# 10-Power.net
KiCad netlist of a schematic drawn in Altium Designer
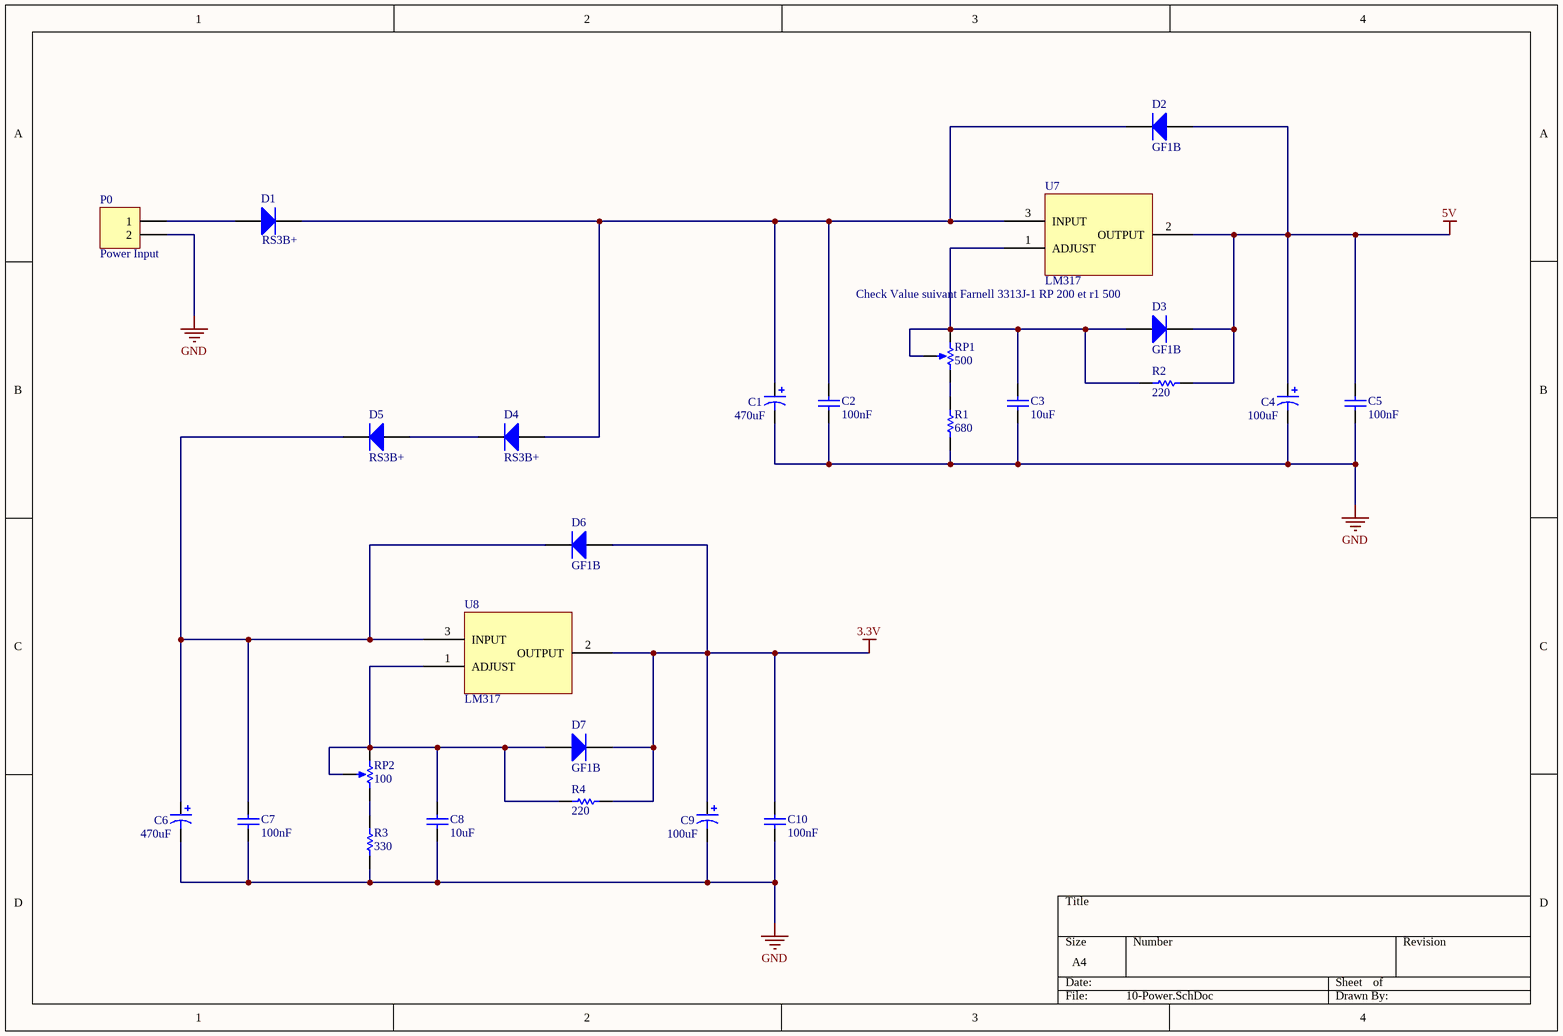
[diagram p0: 10-Power.SchDoc]

(export (version "E")
  (design (tool "Eeschema 10.0.6"))
  (components
    (comp (ref "C1")
      (value "470uF")
      (footprint "CAPA PANA SIZE D*")
      (description "Polarized Capacitor (Radial)")
      (libsource (lib "Miscellaneous Devices") (part "Cap Pol1"))
    )
    (comp (ref "C2")
      (value "100nF")
      (footprint "capa 1206")
      (description "Capacitor")
      (libsource (lib "Miscellaneous Devices") (part "Cap"))
    )
    (comp (ref "C3")
      (value "10uF")
      (footprint "capa 1206")
      (description "Capacitor")
      (libsource (lib "Miscellaneous Devices") (part "Cap"))
    )
    (comp (ref "C4")
      (value "100uF")
      (footprint "CAPA PANA SIZE D*")
      (description "Polarized Capacitor (Radial)")
      (libsource (lib "Miscellaneous Devices") (part "Cap Pol1"))
    )
    (comp (ref "C5")
      (value "100nF")
      (footprint "capa 1206")
      (description "Capacitor")
      (libsource (lib "Miscellaneous Devices") (part "Cap"))
    )
    (comp (ref "C6")
      (value "470uF")
      (footprint "CAPA PANA SIZE D*")
      (description "Polarized Capacitor (Radial)")
      (libsource (lib "Miscellaneous Devices") (part "Cap Pol1"))
    )
    (comp (ref "C7")
      (value "100nF")
      (footprint "capa 1206")
      (description "Capacitor")
      (libsource (lib "Miscellaneous Devices") (part "Cap"))
    )
    (comp (ref "C8")
      (value "10uF")
      (footprint "capa 1206")
      (description "Capacitor")
      (libsource (lib "Miscellaneous Devices") (part "Cap"))
    )
    (comp (ref "C9")
      (value "100uF")
      (footprint "CAPA PANA SIZE D*")
      (description "Polarized Capacitor (Radial)")
      (libsource (lib "Miscellaneous Devices") (part "Cap Pol1"))
    )
    (comp (ref "C10")
      (value "100nF")
      (footprint "capa 1206")
      (description "Capacitor")
      (libsource (lib "Miscellaneous Devices") (part "Cap"))
    )
    (comp (ref "D1")
      (value "RS3B+")
      (footprint "SMC Vishay")
      (description "Default Diode")
      (libsource (lib "Miscellaneous Devices") (part "Diode"))
    )
    (comp (ref "D2")
      (value "GF1B")
      (footprint "DO-214AC(SMA)")
      (description "Default Diode")
      (libsource (lib "Miscellaneous Devices") (part "Diode"))
    )
    (comp (ref "D3")
      (value "GF1B")
      (footprint "DO-214AC(SMA)")
      (description "Default Diode")
      (libsource (lib "Miscellaneous Devices") (part "Diode"))
    )
    (comp (ref "D4")
      (value "RS3B+")
      (footprint "SMC Vishay")
      (description "Default Diode")
      (libsource (lib "Miscellaneous Devices") (part "Diode"))
    )
    (comp (ref "D5")
      (value "RS3B+")
      (footprint "SMC Vishay")
      (description "Default Diode")
      (libsource (lib "Miscellaneous Devices") (part "Diode"))
    )
    (comp (ref "D6")
      (value "GF1B")
      (footprint "DO-214AC(SMA)")
      (description "Default Diode")
      (libsource (lib "Miscellaneous Devices") (part "Diode"))
    )
    (comp (ref "D7")
      (value "GF1B")
      (footprint "DO-214AC(SMA)")
      (description "Default Diode")
      (libsource (lib "Miscellaneous Devices") (part "Diode"))
    )
    (comp (ref "P0")
      (value "Power Input")
      (footprint "PWR")
      (description "Header, 2-Pin")
      (libsource (lib "Miscellaneous Connectors") (part "Header 2"))
    )
    (comp (ref "R1")
      (value "680")
      (footprint "RES 1206")
      (description "Resistor")
      (libsource (lib "Miscellaneous Devices") (part "Res1"))
    )
    (comp (ref "R2")
      (value "220")
      (footprint "RES 1206")
      (description "Resistor")
      (libsource (lib "Miscellaneous Devices") (part "Res1"))
    )
    (comp (ref "R3")
      (value "330")
      (footprint "RES 1206")
      (description "Resistor")
      (libsource (lib "Miscellaneous Devices") (part "Res1"))
    )
    (comp (ref "R4")
      (value "220")
      (footprint "RES 1206")
      (description "Resistor")
      (libsource (lib "Miscellaneous Devices") (part "Res1"))
    )
    (comp (ref "RP1")
      (value "500")
      (footprint "3313J-1")
      (description "Potentiometer")
      (libsource (lib "Miscellaneous Devices") (part "RPot"))
    )
    (comp (ref "RP2")
      (value "100")
      (footprint "3313J-1")
      (description "Potentiometer")
      (libsource (lib "Miscellaneous Devices") (part "RPot"))
    )
    (comp (ref "U7") (value "LM317") (footprint "D2PAK") (libsource (lib "0x2a002a") (part "LM317")))
    (comp (ref "U8") (value "LM317") (footprint "D2PAK") (libsource (lib "0x2a002a") (part "LM317")))
  )
  (nets
    (net (code "1") (name "3.3V") (class "Default")
      (node (ref "C10") (pin "2") (pinfunction "2_2") (pintype "passive"))
      (node (ref "C9") (pin "1") (pinfunction "1_1") (pintype "passive"))
      (node (ref "D6") (pin "1") (pinfunction "A_1") (pintype "passive"))
      (node (ref "D7") (pin "2") (pinfunction "K_2") (pintype "passive"))
      (node (ref "R4") (pin "1") (pinfunction "1_1") (pintype "passive"))
      (node (ref "U8") (pin "2") (pinfunction "OUTPUT_2") (pintype "power_in"))
    )
    (net (code "2") (name "5V") (class "Default")
      (node (ref "C4") (pin "1") (pinfunction "1_1") (pintype "passive"))
      (node (ref "C5") (pin "2") (pinfunction "2_2") (pintype "passive"))
      (node (ref "D2") (pin "1") (pinfunction "A_1") (pintype "passive"))
      (node (ref "D3") (pin "2") (pinfunction "K_2") (pintype "passive"))
      (node (ref "R2") (pin "1") (pinfunction "1_1") (pintype "passive"))
      (node (ref "U7") (pin "2") (pinfunction "OUTPUT_2") (pintype "power_in"))
    )
    (net (code "3") (name "GND") (class "Default")
      (node (ref "C1") (pin "2") (pinfunction "2_2") (pintype "passive"))
      (node (ref "C10") (pin "1") (pinfunction "1_1") (pintype "passive"))
      (node (ref "C2") (pin "1") (pinfunction "1_1") (pintype "passive"))
      (node (ref "C3") (pin "1") (pinfunction "1_1") (pintype "passive"))
      (node (ref "C4") (pin "2") (pinfunction "2_2") (pintype "passive"))
      (node (ref "C5") (pin "1") (pinfunction "1_1") (pintype "passive"))
      (node (ref "C6") (pin "2") (pinfunction "2_2") (pintype "passive"))
      (node (ref "C7") (pin "1") (pinfunction "1_1") (pintype "passive"))
      (node (ref "C8") (pin "1") (pinfunction "1_1") (pintype "passive"))
      (node (ref "C9") (pin "2") (pinfunction "2_2") (pintype "passive"))
      (node (ref "P0") (pin "2") (pinfunction "2_2") (pintype "passive"))
      (node (ref "R1") (pin "1") (pinfunction "1_1") (pintype "passive"))
      (node (ref "R3") (pin "2") (pinfunction "2_2") (pintype "passive"))
    )
    (net (code "4") (name "Net-(D1-A)") (class "Default")
      (node (ref "D1") (pin "1") (pinfunction "A_1") (pintype "passive"))
      (node (ref "P0") (pin "1") (pinfunction "1_1") (pintype "passive"))
    )
    (net (code "5") (name "Net-(D1-K)") (class "Default")
      (node (ref "C1") (pin "1") (pinfunction "1_1") (pintype "passive"))
      (node (ref "C2") (pin "2") (pinfunction "2_2") (pintype "passive"))
      (node (ref "D1") (pin "2") (pinfunction "K_2") (pintype "passive"))
      (node (ref "D2") (pin "2") (pinfunction "K_2") (pintype "passive"))
      (node (ref "D4") (pin "1") (pinfunction "A_1") (pintype "passive"))
      (node (ref "U7") (pin "3") (pinfunction "INPUT_3") (pintype "power_in"))
    )
    (net (code "6") (name "Net-(D3-A)") (class "Default")
      (node (ref "C3") (pin "2") (pinfunction "2_2") (pintype "passive"))
      (node (ref "D3") (pin "1") (pinfunction "A_1") (pintype "passive"))
      (node (ref "R2") (pin "2") (pinfunction "2_2") (pintype "passive"))
      (node (ref "RP1") (pin "1") (pinfunction "TOP_1") (pintype "passive"))
      (node (ref "RP1") (pin "3") (pinfunction "TAP_3") (pintype "passive"))
      (node (ref "U7") (pin "1") (pinfunction "ADJUST_1") (pintype "power_in"))
    )
    (net (code "7") (name "Net-(D4-K)") (class "Default")
      (node (ref "D4") (pin "2") (pinfunction "K_2") (pintype "passive"))
      (node (ref "D5") (pin "1") (pinfunction "A_1") (pintype "passive"))
    )
    (net (code "8") (name "Net-(D5-K)") (class "Default")
      (node (ref "C6") (pin "1") (pinfunction "1_1") (pintype "passive"))
      (node (ref "C7") (pin "2") (pinfunction "2_2") (pintype "passive"))
      (node (ref "D5") (pin "2") (pinfunction "K_2") (pintype "passive"))
      (node (ref "D6") (pin "2") (pinfunction "K_2") (pintype "passive"))
      (node (ref "U8") (pin "3") (pinfunction "INPUT_3") (pintype "power_in"))
    )
    (net (code "9") (name "Net-(D7-A)") (class "Default")
      (node (ref "C8") (pin "2") (pinfunction "2_2") (pintype "passive"))
      (node (ref "D7") (pin "1") (pinfunction "A_1") (pintype "passive"))
      (node (ref "R4") (pin "2") (pinfunction "2_2") (pintype "passive"))
      (node (ref "RP2") (pin "1") (pinfunction "TOP_1") (pintype "passive"))
      (node (ref "RP2") (pin "3") (pinfunction "TAP_3") (pintype "passive"))
      (node (ref "U8") (pin "1") (pinfunction "ADJUST_1") (pintype "power_in"))
    )
    (net (code "10") (name "Net-(RP1-BOT)") (class "Default")
      (node (ref "R1") (pin "2") (pinfunction "2_2") (pintype "passive"))
      (node (ref "RP1") (pin "2") (pinfunction "BOT_2") (pintype "passive"))
    )
    (net (code "11") (name "Net-(RP2-BOT)") (class "Default")
      (node (ref "R3") (pin "1") (pinfunction "1_1") (pintype "passive"))
      (node (ref "RP2") (pin "2") (pinfunction "BOT_2") (pintype "passive"))
    )
  )
)
